# AD9833.net
KiCad netlist of a schematic drawn in Altium Designer
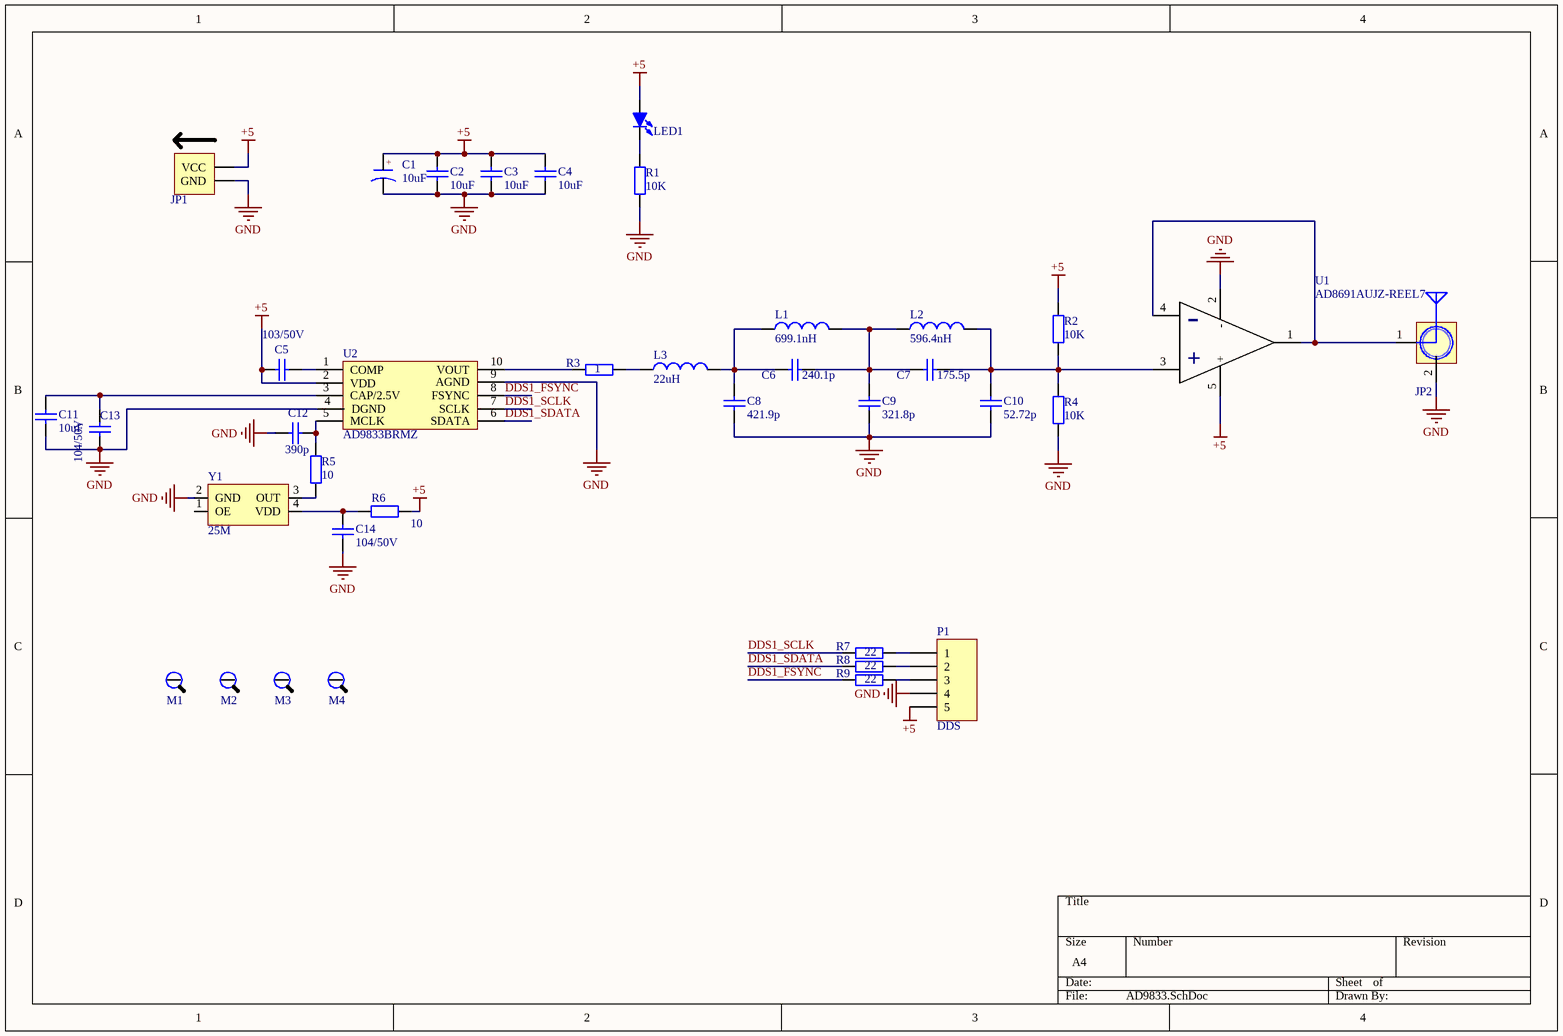
[diagram p0: AD9833.SchDoc]

(export (version "E")
  (design (tool "Eeschema 10.0.6"))
  (components
    (comp (ref "C1")
      (value "10uF")
      (footprint "CASE-A_3216")
      (description "贴片钽电容")
      (fields (field (name "Comment") "CAP+"))
      (libsource (lib "Cooperation") (part "0CAP+"))
    )
    (comp (ref "C2")
      (value "10uF")
      (footprint "C0603")
      (description "小功率贴片电容")
      (fields (field (name "Comment") "CAP"))
      (libsource (lib "Cooperation") (part "0CAP"))
    )
    (comp (ref "C3")
      (value "10uF")
      (footprint "C0603")
      (description "小功率贴片电容")
      (fields (field (name "Comment") "CAP"))
      (libsource (lib "Cooperation") (part "0CAP"))
    )
    (comp (ref "C4")
      (value "10uF")
      (footprint "C0603")
      (description "小功率贴片电容")
      (fields (field (name "Comment") "CAP"))
      (libsource (lib "Cooperation") (part "0CAP"))
    )
    (comp (ref "C5")
      (value "103/50V")
      (footprint "C0603")
      (description "贴片电容")
      (libsource (lib "JLC") (part "0603 10nF (103) 10% 50V"))
    )
    (comp (ref "C6")
      (value "240.1p")
      (footprint "C0603")
      (description "Capacitor")
      (fields (field (name "PUBLISHER") "Altium Limited"))
      (libsource (lib "Miscellaneous Devices") (part "Cap"))
    )
    (comp (ref "C7")
      (value "175.5p")
      (footprint "C0603")
      (description "Capacitor")
      (fields (field (name "PUBLISHER") "Altium Limited"))
      (libsource (lib "Miscellaneous Devices") (part "Cap"))
    )
    (comp (ref "C8")
      (value "421.9p")
      (footprint "C0603")
      (description "Capacitor")
      (fields (field (name "PUBLISHER") "Altium Limited"))
      (libsource (lib "Miscellaneous Devices") (part "Cap"))
    )
    (comp (ref "C9")
      (value "321.8p")
      (footprint "C0603")
      (description "Capacitor")
      (fields (field (name "PUBLISHER") "Altium Limited"))
      (libsource (lib "Miscellaneous Devices") (part "Cap"))
    )
    (comp (ref "C10")
      (value "52.72p")
      (footprint "C0603")
      (description "Capacitor")
      (fields (field (name "PUBLISHER") "Altium Limited"))
      (libsource (lib "Miscellaneous Devices") (part "Cap"))
    )
    (comp (ref "C11")
      (value "10uF")
      (footprint "C0603")
      (description "小功率贴片电容")
      (fields (field (name "Comment") "CAP"))
      (libsource (lib "Cooperation") (part "0CAP"))
    )
    (comp (ref "C12")
      (value "390p")
      (footprint "C0603")
      (description "贴片电容")
      (libsource (lib "JLC") (part "0603 100nF (104) 10% 50V"))
    )
    (comp (ref "C13")
      (value "104/50V")
      (footprint "C0603")
      (description "贴片电容")
      (libsource (lib "JLC") (part "0603 100nF (104) 10% 50V"))
    )
    (comp (ref "C14")
      (value "104/50V")
      (footprint "C0603")
      (description "贴片电容")
      (libsource (lib "JLC") (part "0603 100nF (104) 10% 50V"))
    )
    (comp (ref "JP1")
      (value "HDR-1X2")
      (footprint "Power_IN_3.81-2P")
      (description "2P接插件,模块单电源供电口")
      (fields (field (name "版权归属") "源创客"))
      (libsource (lib "Cooperation") (part "PORT_Power_IN2"))
    )
    (comp (ref "JP2")
      (value "SMA WIFI 天线接口")
      (footprint "SMA")
      (description "SMA-2.4G射频天线接口")
      (fields (field (name "版权归属") "源创客"))
      (libsource (lib "Cooperation") (part "PORT_SMA"))
    )
    (comp (ref "L1")
      (value "699.1nH")
      (footprint "L-0603")
      (description "Inductor")
      (fields (field (name "PUBLISHER") "Altium Limited"))
      (libsource (lib "Miscellaneous Devices") (part "Inductor"))
    )
    (comp (ref "L2")
      (value "596.4nH")
      (footprint "L-0603")
      (description "Inductor")
      (fields (field (name "PUBLISHER") "Altium Limited"))
      (libsource (lib "Miscellaneous Devices") (part "Inductor"))
    )
    (comp (ref "L3")
      (value "22uH")
      (footprint "L-0603")
      (description "Inductor")
      (fields (field (name "PUBLISHER") "Altium Limited"))
      (libsource (lib "Miscellaneous Devices") (part "Inductor"))
    )
    (comp (ref "LED1")
      (value "红色")
      (footprint "LED 0603")
      (description "贴片LED")
      (libsource (lib "Cooperation") (part "ELSE_LED_SMD"))
    )
    (comp (ref "M1")
      (value "M3")
      (footprint "M3x10_L")
      (description "螺丝")
      (libsource (lib "Cooperation") (part "ELSE_M3_screw"))
    )
    (comp (ref "M2")
      (value "M3")
      (footprint "M3x10_L")
      (description "螺丝")
      (libsource (lib "Cooperation") (part "ELSE_M3_screw"))
    )
    (comp (ref "M3")
      (value "M3")
      (footprint "M3x10_L")
      (description "螺丝")
      (libsource (lib "Cooperation") (part "ELSE_M3_screw"))
    )
    (comp (ref "M4")
      (value "M3")
      (footprint "M3x10_L")
      (description "螺丝")
      (libsource (lib "Cooperation") (part "ELSE_M3_screw"))
    )
    (comp (ref "P1")
      (value "DDS")
      (footprint "HDR1X5")
      (description "Header, 5-Pin")
      (fields (field (name "PUBLISHER") "Altium Limited"))
      (libsource (lib "Miscellaneous Connectors") (part "Header 5"))
    )
    (comp (ref "R1")
      (value "10K")
      (footprint "R-0805")
      (description "小功率贴片电组")
      (fields (field (name "Comment") "Res"))
      (libsource (lib "Cooperation") (part "0RES"))
    )
    (comp (ref "R2")
      (value "10K")
      (footprint "R-0805")
      (description "小功率贴片电组")
      (fields (field (name "Comment") "Res"))
      (libsource (lib "Cooperation") (part "0RES"))
    )
    (comp (ref "R3")
      (value "1")
      (footprint "0603_R")
      (description "贴片电阻")
      (libsource (lib "JLC") (part "0603 10Ω (10R0) 1%"))
    )
    (comp (ref "R4")
      (value "10K")
      (footprint "R-0805")
      (description "小功率贴片电组")
      (fields (field (name "Comment") "Res"))
      (libsource (lib "Cooperation") (part "0RES"))
    )
    (comp (ref "R5")
      (value "10")
      (footprint "0603_R")
      (description "贴片电阻")
      (libsource (lib "") (part "0603 10Ω (10R0) 1%_1"))
    )
    (comp (ref "R6")
      (value "10")
      (footprint "0603_R")
      (description "贴片电阻")
      (libsource (lib "JLC") (part "0603 10Ω (10R0) 1%"))
    )
    (comp (ref "R7")
      (value "22")
      (footprint "0603_R")
      (description "贴片电阻")
      (libsource (lib "JLC") (part "0603 10Ω (10R0) 1%"))
    )
    (comp (ref "R8")
      (value "22")
      (footprint "0603_R")
      (description "贴片电阻")
      (libsource (lib "JLC") (part "0603 10Ω (10R0) 1%"))
    )
    (comp (ref "R9")
      (value "22")
      (footprint "0603_R")
      (description "贴片电阻")
      (libsource (lib "JLC") (part "0603 10Ω (10R0) 1%"))
    )
    (comp (ref "U1")
      (value "AD8691AUJZ-REEL7")
      (footprint "SOT23-5N")
      (libsource (lib "Integrated_Library") (part "AD8691AUJZ-REEL7"))
    )
    (comp (ref "U2")
      (value "AD9833BRMZ")
      (footprint "MSOP10_L")
      (libsource (lib "cooperation") (part "AD9833BRMZ"))
    )
    (comp (ref "Y1")
      (value "25M")
      (footprint "OSC 3225-4P")
      (description "贴片有源晶振")
      (libsource (lib "主集成库") (part "XATLS"))
    )
  )
  (nets
    (net (code "1") (name "+5") (class "Default")
      (node (ref "C1") (pin "1") (pinfunction "A_1") (pintype "passive"))
      (node (ref "C2") (pin "2") (pinfunction "2_2") (pintype "passive"))
      (node (ref "C3") (pin "2") (pinfunction "2_2") (pintype "passive"))
      (node (ref "C4") (pin "2") (pinfunction "2_2") (pintype "passive"))
      (node (ref "C5") (pin "1") (pinfunction "1_1") (pintype "passive"))
      (node (ref "JP1") (pin "1") (pinfunction "VCC_1") (pintype "passive"))
      (node (ref "LED1") (pin "1") (pinfunction "A_1") (pintype "passive"))
      (node (ref "P1") (pin "5") (pinfunction "5_5") (pintype "passive"))
      (node (ref "R2") (pin "2") (pinfunction "2_2") (pintype "passive"))
      (node (ref "R6") (pin "2") (pinfunction "2_2") (pintype "passive"))
      (node (ref "U1") (pin "5") (pinfunction "+_5") (pintype "passive"))
      (node (ref "U2") (pin "2") (pinfunction "VDD_2") (pintype "passive"))
    )
    (net (code "2") (name "/DDS1_FSYNC") (class "Default")
      (node (ref "R9") (pin "1") (pinfunction "1_1") (pintype "passive"))
      (node (ref "U2") (pin "8") (pinfunction "FSYNC_8") (pintype "passive"))
    )
    (net (code "3") (name "/DDS1_SCLK") (class "Default")
      (node (ref "R7") (pin "1") (pinfunction "1_1") (pintype "passive"))
      (node (ref "U2") (pin "7") (pinfunction "SCLK_7") (pintype "passive"))
    )
    (net (code "4") (name "/DDS1_SDATA") (class "Default")
      (node (ref "R8") (pin "1") (pinfunction "1_1") (pintype "passive"))
      (node (ref "U2") (pin "6") (pinfunction "SDATA_6") (pintype "passive"))
    )
    (net (code "5") (name "GND") (class "Default")
      (node (ref "C1") (pin "2") (pinfunction "K_2") (pintype "passive"))
      (node (ref "C10") (pin "1") (pinfunction "1_1") (pintype "passive"))
      (node (ref "C11") (pin "1") (pinfunction "1_1") (pintype "passive"))
      (node (ref "C12") (pin "2") (pinfunction "2_2") (pintype "passive"))
      (node (ref "C13") (pin "1") (pinfunction "1_1") (pintype "passive"))
      (node (ref "C14") (pin "1") (pinfunction "1_1") (pintype "passive"))
      (node (ref "C2") (pin "1") (pinfunction "1_1") (pintype "passive"))
      (node (ref "C3") (pin "1") (pinfunction "1_1") (pintype "passive"))
      (node (ref "C4") (pin "1") (pinfunction "1_1") (pintype "passive"))
      (node (ref "C8") (pin "1") (pinfunction "1_1") (pintype "passive"))
      (node (ref "C9") (pin "1") (pinfunction "1_1") (pintype "passive"))
      (node (ref "JP1") (pin "2") (pinfunction "GND_2") (pintype "passive"))
      (node (ref "JP2") (pin "2") (pinfunction "2_2") (pintype "passive"))
      (node (ref "P1") (pin "4") (pinfunction "4_4") (pintype "passive"))
      (node (ref "R1") (pin "1") (pinfunction "1_1") (pintype "passive"))
      (node (ref "R4") (pin "1") (pinfunction "1_1") (pintype "passive"))
      (node (ref "U1") (pin "2") (pinfunction "-_2") (pintype "passive"))
      (node (ref "U2") (pin "4") (pinfunction "DGND_4") (pintype "passive"))
      (node (ref "U2") (pin "9") (pinfunction "AGND_9") (pintype "passive"))
      (node (ref "Y1") (pin "2") (pinfunction "GND_2") (pintype "passive"))
    )
    (net (code "6") (name "Net-(C6-Pad1)") (class "Default")
      (node (ref "C6") (pin "1") (pinfunction "1_1") (pintype "passive"))
      (node (ref "C7") (pin "2") (pinfunction "2_2") (pintype "passive"))
      (node (ref "C9") (pin "2") (pinfunction "2_2") (pintype "passive"))
      (node (ref "L1") (pin "2") (pinfunction "2_2") (pintype "passive"))
      (node (ref "L2") (pin "1") (pinfunction "1_1") (pintype "passive"))
    )
    (net (code "7") (name "Net-(C6-Pad2)") (class "Default")
      (node (ref "C6") (pin "2") (pinfunction "2_2") (pintype "passive"))
      (node (ref "C8") (pin "2") (pinfunction "2_2") (pintype "passive"))
      (node (ref "L1") (pin "1") (pinfunction "1_1") (pintype "passive"))
      (node (ref "L3") (pin "2") (pinfunction "2_2") (pintype "passive"))
    )
    (net (code "8") (name "Net-(JP2-SINGLE)") (class "Default")
      (node (ref "JP2") (pin "1") (pinfunction "SINGLE_1") (pintype "passive"))
      (node (ref "U1") (pin "1") (pinfunction "OUT_1") (pintype "passive"))
      (node (ref "U1") (pin "4") (pinfunction "IN-_4") (pintype "passive"))
    )
    (net (code "9") (name "Net-(L3-Pad1)") (class "Default")
      (node (ref "L3") (pin "1") (pinfunction "1_1") (pintype "passive"))
      (node (ref "R3") (pin "2") (pinfunction "2_2") (pintype "passive"))
    )
    (net (code "10") (name "Net-(LED1-K)") (class "Default")
      (node (ref "LED1") (pin "2") (pinfunction "K_2") (pintype "passive"))
      (node (ref "R1") (pin "2") (pinfunction "2_2") (pintype "passive"))
    )
    (net (code "11") (name "Net-(P1-Pad1)") (class "Default")
      (node (ref "P1") (pin "1") (pinfunction "1_1") (pintype "passive"))
      (node (ref "R7") (pin "2") (pinfunction "2_2") (pintype "passive"))
    )
    (net (code "12") (name "Net-(P1-Pad2)") (class "Default")
      (node (ref "P1") (pin "2") (pinfunction "2_2") (pintype "passive"))
      (node (ref "R8") (pin "2") (pinfunction "2_2") (pintype "passive"))
    )
    (net (code "13") (name "Net-(P1-Pad3)") (class "Default")
      (node (ref "P1") (pin "3") (pinfunction "3_3") (pintype "passive"))
      (node (ref "R9") (pin "2") (pinfunction "2_2") (pintype "passive"))
    )
    (net (code "14") (name "Net-(U1-IN+)") (class "Default")
      (node (ref "C10") (pin "2") (pinfunction "2_2") (pintype "passive"))
      (node (ref "C7") (pin "1") (pinfunction "1_1") (pintype "passive"))
      (node (ref "L2") (pin "2") (pinfunction "2_2") (pintype "passive"))
      (node (ref "R2") (pin "1") (pinfunction "1_1") (pintype "passive"))
      (node (ref "R4") (pin "2") (pinfunction "2_2") (pintype "passive"))
      (node (ref "U1") (pin "3") (pinfunction "IN+_3") (pintype "passive"))
    )
    (net (code "15") (name "Net-(U2-CAP{slash}2.5V)") (class "Default")
      (node (ref "C11") (pin "2") (pinfunction "2_2") (pintype "passive"))
      (node (ref "C13") (pin "2") (pinfunction "2_2") (pintype "passive"))
      (node (ref "U2") (pin "3") (pinfunction "CAP/2.5V_3") (pintype "passive"))
    )
    (net (code "16") (name "Net-(U2-COMP)") (class "Default")
      (node (ref "C5") (pin "2") (pinfunction "2_2") (pintype "passive"))
      (node (ref "U2") (pin "1") (pinfunction "COMP_1") (pintype "passive"))
    )
    (net (code "17") (name "Net-(U2-MCLK)") (class "Default")
      (node (ref "C12") (pin "1") (pinfunction "1_1") (pintype "passive"))
      (node (ref "R5") (pin "2") (pinfunction "2_2") (pintype "passive"))
      (node (ref "U2") (pin "5") (pinfunction "MCLK_5") (pintype "passive"))
    )
    (net (code "18") (name "Net-(U2-VOUT)") (class "Default")
      (node (ref "R3") (pin "1") (pinfunction "1_1") (pintype "passive"))
      (node (ref "U2") (pin "10") (pinfunction "VOUT_10") (pintype "passive"))
    )
    (net (code "19") (name "Net-(Y1-OUT)") (class "Default")
      (node (ref "R5") (pin "1") (pinfunction "1_1") (pintype "passive"))
      (node (ref "Y1") (pin "3") (pinfunction "OUT_3") (pintype "passive"))
    )
    (net (code "20") (name "Net-(Y1-VDD)") (class "Default")
      (node (ref "C14") (pin "2") (pinfunction "2_2") (pintype "passive"))
      (node (ref "R6") (pin "1") (pinfunction "1_1") (pintype "passive"))
      (node (ref "Y1") (pin "4") (pinfunction "VDD_4") (pintype "passive"))
    )
    (net (code "21") (name "unconnected-(M1-Pad1)") (class "Default")
      (node (ref "M1") (pin "1") (pinfunction "1_1") (pintype "passive"))
    )
    (net (code "22") (name "unconnected-(M2-Pad1)") (class "Default")
      (node (ref "M2") (pin "1") (pinfunction "1_1") (pintype "passive"))
    )
    (net (code "23") (name "unconnected-(M3-Pad1)") (class "Default")
      (node (ref "M3") (pin "1") (pinfunction "1_1") (pintype "passive"))
    )
    (net (code "24") (name "unconnected-(M4-Pad1)") (class "Default")
      (node (ref "M4") (pin "1") (pinfunction "1_1") (pintype "passive"))
    )
    (net (code "25") (name "unconnected-(Y1-OE-Pad1)") (class "Default")
      (node (ref "Y1") (pin "1") (pinfunction "OE_1") (pintype "passive"))
    )
  )
)
